# Boardv2.net
KiCad netlist of a schematic drawn in EAGLE
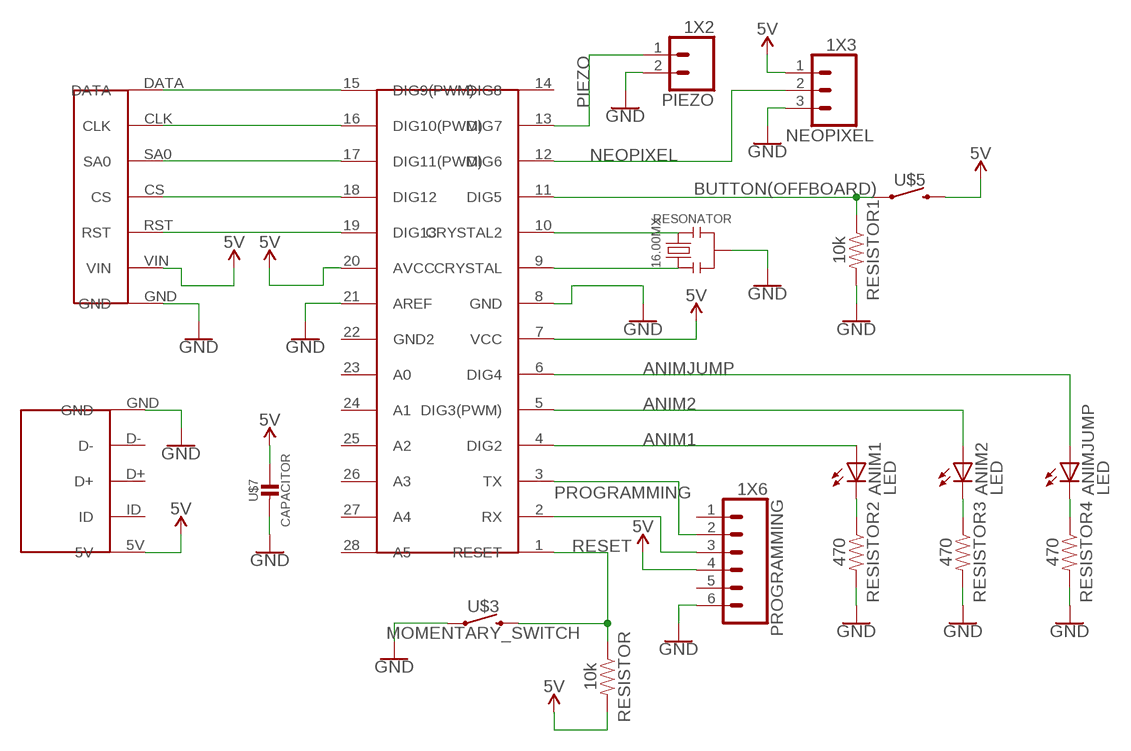
[diagram p0: schematic, sheet 1]

(export (version "E")
  (design (tool "Eeschema 10.0.6"))
  (components
    (comp (ref "16.00MX")
      (value "RESONATOR")
      (footprint "eagle-import:1X03_NO_SILK")
      (libsource (lib "eagle-import") (part "RESONATOR"))
    )
    (comp (ref "ANIM1")
      (value "LED")
      (footprint "eagle-import:1X02_LONGPADS")
      (libsource (lib "eagle-import") (part "LED"))
    )
    (comp (ref "ANIM2")
      (value "LED")
      (footprint "eagle-import:1X02_LONGPADS")
      (libsource (lib "eagle-import") (part "LED"))
    )
    (comp (ref "ANIMJUMP")
      (value "LED")
      (footprint "eagle-import:1X02_LONGPADS")
      (libsource (lib "eagle-import") (part "LED"))
    )
    (comp (ref "NEOPIXEL")
      (value "1X3")
      (footprint "eagle-import:1X03_NO_SILK")
      (libsource (lib "eagle-import") (part "1X3"))
    )
    (comp (ref "PIEZO")
      (value "1X2")
      (footprint "eagle-import:1X02_LONGPADS")
      (libsource (lib "eagle-import") (part "1X2"))
    )
    (comp (ref "PROGRAMMING")
      (value "1X6")
      (footprint "eagle-import:1X06_NO_SILK")
      (libsource (lib "eagle-import") (part "1X6"))
    )
    (comp (ref "RESISTOR")
      (value "10k")
      (footprint "eagle-import:AXIAL-0.3")
      (libsource (lib "eagle-import") (part "RESISTOR"))
    )
    (comp (ref "RESISTOR1")
      (value "10k")
      (footprint "eagle-import:AXIAL-0.3")
      (libsource (lib "eagle-import") (part "RESISTOR"))
    )
    (comp (ref "RESISTOR2")
      (value "470")
      (footprint "eagle-import:AXIAL-0.3")
      (libsource (lib "eagle-import") (part "RESISTOR"))
    )
    (comp (ref "RESISTOR3")
      (value "470")
      (footprint "eagle-import:AXIAL-0.3")
      (libsource (lib "eagle-import") (part "RESISTOR"))
    )
    (comp (ref "RESISTOR4")
      (value "470")
      (footprint "eagle-import:AXIAL-0.3")
      (libsource (lib "eagle-import") (part "RESISTOR"))
    )
    (comp (ref "U$1")
      (value "ATMEGA328")
      (footprint "eagle-import:ATMEGA328")
      (libsource (lib "eagle-import") (part "ATMEGA328"))
    )
    (comp (ref "U$2")
      (value "USB")
      (footprint "eagle-import:USB")
      (libsource (lib "eagle-import") (part "USB"))
    )
    (comp (ref "U$3")
      (value "MOMENTARY_SWITCH")
      (footprint "eagle-import:TACTILE_SWITCH_PTH_6.0MM")
      (libsource (lib "eagle-import") (part "MOMENTARY_SWITCH"))
    )
    (comp (ref "U$5")
      (value "BUTTON(OFFBOARD)")
      (footprint "eagle-import:1X02_LONGPADS")
      (libsource (lib "eagle-import") (part "BUTTON(OFFBOARD)"))
    )
    (comp (ref "U$6")
      (value "OLED")
      (footprint "eagle-import:OLED")
      (libsource (lib "eagle-import") (part "OLED"))
    )
    (comp (ref "U$7")
      (value "CAPACITOR")
      (footprint "eagle-import:1X02_LONGPADS")
      (libsource (lib "eagle-import") (part "CAPACITOR"))
    )
  )
  (nets
    (net (code "1") (name "/ANIM1") (class "Default")
      (node (ref "ANIM1") (pin "1") (pinfunction "A_1") (pintype "passive"))
      (node (ref "U$1") (pin "4") (pinfunction "DIG2_4") (pintype "bidirectional"))
    )
    (net (code "2") (name "/ANIM2") (class "Default")
      (node (ref "ANIM2") (pin "1") (pinfunction "A_1") (pintype "passive"))
      (node (ref "U$1") (pin "5") (pinfunction "DIG3(PWM)_5") (pintype "bidirectional"))
    )
    (net (code "3") (name "/ANIMJUMP") (class "Default")
      (node (ref "ANIMJUMP") (pin "1") (pinfunction "A_1") (pintype "passive"))
      (node (ref "U$1") (pin "6") (pinfunction "DIG4_6") (pintype "bidirectional"))
    )
    (net (code "4") (name "/NEOPIXEL") (class "Default")
      (node (ref "NEOPIXEL") (pin "2") (pinfunction "2_2") (pintype "passive"))
      (node (ref "U$1") (pin "12") (pinfunction "DIG6_12") (pintype "bidirectional"))
    )
    (net (code "5") (name "/PIEZO") (class "Default")
      (node (ref "PIEZO") (pin "1") (pinfunction "1_1") (pintype "passive"))
      (node (ref "U$1") (pin "13") (pinfunction "DIG7_13") (pintype "bidirectional"))
    )
    (net (code "6") (name "/PROGRAMMING") (class "Default")
      (node (ref "PROGRAMMING") (pin "2") (pinfunction "2_2") (pintype "passive"))
      (node (ref "U$1") (pin "3") (pinfunction "TX_3") (pintype "bidirectional"))
    )
    (net (code "7") (name "/RESET") (class "Default")
      (node (ref "RESISTOR") (pin "P$1") (pinfunction "1_P$1") (pintype "passive"))
      (node (ref "U$1") (pin "1") (pinfunction "RESET_1") (pintype "bidirectional"))
      (node (ref "U$3") (pin "3") (pinfunction "2_3") (pintype "passive"))
      (node (ref "U$3") (pin "4") (pinfunction "2_4") (pintype "passive"))
    )
    (net (code "8") (name "5V") (class "Default")
      (node (ref "NEOPIXEL") (pin "1") (pinfunction "1_1") (pintype "passive"))
      (node (ref "PROGRAMMING") (pin "4") (pinfunction "4_4") (pintype "passive"))
      (node (ref "RESISTOR") (pin "P$2") (pinfunction "2_P$2") (pintype "passive"))
      (node (ref "U$1") (pin "20") (pinfunction "AVCC_20") (pintype "bidirectional"))
      (node (ref "U$1") (pin "7") (pinfunction "VCC_7") (pintype "bidirectional"))
      (node (ref "U$2") (pin "5V") (pinfunction "5V_5V") (pintype "bidirectional"))
      (node (ref "U$5") (pin "2") (pinfunction "2_2") (pintype "passive"))
      (node (ref "U$6") (pin "VIN") (pinfunction "VIN_VIN") (pintype "bidirectional"))
      (node (ref "U$7") (pin "1") (pinfunction "1_1") (pintype "passive"))
    )
    (net (code "9") (name "GND") (class "Default")
      (node (ref "16.00MX") (pin "2") (pinfunction "2_2") (pintype "passive"))
      (node (ref "NEOPIXEL") (pin "3") (pinfunction "3_3") (pintype "passive"))
      (node (ref "PIEZO") (pin "2") (pinfunction "2_2") (pintype "passive"))
      (node (ref "PROGRAMMING") (pin "6") (pinfunction "6_6") (pintype "passive"))
      (node (ref "RESISTOR1") (pin "P$2") (pinfunction "2_P$2") (pintype "passive"))
      (node (ref "RESISTOR2") (pin "P$2") (pinfunction "2_P$2") (pintype "passive"))
      (node (ref "RESISTOR3") (pin "P$2") (pinfunction "2_P$2") (pintype "passive"))
      (node (ref "RESISTOR4") (pin "P$2") (pinfunction "2_P$2") (pintype "passive"))
      (node (ref "U$1") (pin "21") (pinfunction "AREF_21") (pintype "bidirectional"))
      (node (ref "U$1") (pin "8") (pinfunction "GND_8") (pintype "bidirectional"))
      (node (ref "U$2") (pin "GND") (pinfunction "GND_GND") (pintype "bidirectional"))
      (node (ref "U$3") (pin "1") (pinfunction "1_1") (pintype "passive"))
      (node (ref "U$3") (pin "2") (pinfunction "1_2") (pintype "passive"))
      (node (ref "U$6") (pin "GND") (pinfunction "GND_GND") (pintype "bidirectional"))
      (node (ref "U$7") (pin "2") (pinfunction "2_2") (pintype "passive"))
    )
    (net (code "10") (name "Net-(ANIM1-C)") (class "Default")
      (node (ref "ANIM1") (pin "2") (pinfunction "C_2") (pintype "passive"))
      (node (ref "RESISTOR2") (pin "P$1") (pinfunction "1_P$1") (pintype "passive"))
    )
    (net (code "11") (name "Net-(ANIM2-C)") (class "Default")
      (node (ref "ANIM2") (pin "2") (pinfunction "C_2") (pintype "passive"))
      (node (ref "RESISTOR3") (pin "P$1") (pinfunction "1_P$1") (pintype "passive"))
    )
    (net (code "12") (name "Net-(ANIMJUMP-C)") (class "Default")
      (node (ref "ANIMJUMP") (pin "2") (pinfunction "C_2") (pintype "passive"))
      (node (ref "RESISTOR4") (pin "P$1") (pinfunction "1_P$1") (pintype "passive"))
    )
    (net (code "13") (name "Net-(RESISTOR1-1)") (class "Default")
      (node (ref "RESISTOR1") (pin "P$1") (pinfunction "1_P$1") (pintype "passive"))
      (node (ref "U$1") (pin "11") (pinfunction "DIG5_11") (pintype "bidirectional"))
      (node (ref "U$5") (pin "1") (pinfunction "1_1") (pintype "passive"))
    )
    (net (code "14") (name "Net-(U$1-CRYSTAL)") (class "Default")
      (node (ref "16.00MX") (pin "1") (pinfunction "1_1") (pintype "passive"))
      (node (ref "U$1") (pin "9") (pinfunction "CRYSTAL_9") (pintype "bidirectional"))
    )
    (net (code "15") (name "Net-(U$1-CRYSTAL2)") (class "Default")
      (node (ref "16.00MX") (pin "3") (pinfunction "3_3") (pintype "passive"))
      (node (ref "U$1") (pin "10") (pinfunction "CRYSTAL2_10") (pintype "bidirectional"))
    )
    (net (code "16") (name "Net-(U$1-DIG9(PWM))") (class "Default")
      (node (ref "U$1") (pin "15") (pinfunction "DIG9(PWM)_15") (pintype "bidirectional"))
      (node (ref "U$6") (pin "DATA") (pinfunction "DATA_DATA") (pintype "bidirectional"))
    )
    (net (code "17") (name "Net-(U$1-DIG10(PWM))") (class "Default")
      (node (ref "U$1") (pin "16") (pinfunction "DIG10(PWM)_16") (pintype "bidirectional"))
      (node (ref "U$6") (pin "CLK") (pinfunction "CLK_CLK") (pintype "bidirectional"))
    )
    (net (code "18") (name "Net-(U$1-DIG11(PWM))") (class "Default")
      (node (ref "U$1") (pin "17") (pinfunction "DIG11(PWM)_17") (pintype "bidirectional"))
      (node (ref "U$6") (pin "SA0") (pinfunction "SA0_SA0") (pintype "bidirectional"))
    )
    (net (code "19") (name "Net-(U$1-DIG12)") (class "Default")
      (node (ref "U$1") (pin "18") (pinfunction "DIG12_18") (pintype "bidirectional"))
      (node (ref "U$6") (pin "CS") (pinfunction "CS_CS") (pintype "bidirectional"))
    )
    (net (code "20") (name "Net-(U$1-DIG13)") (class "Default")
      (node (ref "U$1") (pin "19") (pinfunction "DIG13_19") (pintype "bidirectional"))
      (node (ref "U$6") (pin "RST") (pinfunction "RST_RST") (pintype "bidirectional"))
    )
    (net (code "21") (name "Net-(U$1-RX)") (class "Default")
      (node (ref "PROGRAMMING") (pin "3") (pinfunction "3_3") (pintype "passive"))
      (node (ref "U$1") (pin "2") (pinfunction "RX_2") (pintype "bidirectional"))
    )
    (net (code "22") (name "unconnected-(PROGRAMMING-Pad1)") (class "Default")
      (node (ref "PROGRAMMING") (pin "1") (pinfunction "1_1") (pintype "passive"))
    )
    (net (code "23") (name "unconnected-(PROGRAMMING-Pad5)") (class "Default")
      (node (ref "PROGRAMMING") (pin "5") (pinfunction "5_5") (pintype "passive"))
    )
    (net (code "24") (name "unconnected-(U$1-A0-Pad23)") (class "Default")
      (node (ref "U$1") (pin "23") (pinfunction "A0_23") (pintype "bidirectional"))
    )
    (net (code "25") (name "unconnected-(U$1-A1-Pad24)") (class "Default")
      (node (ref "U$1") (pin "24") (pinfunction "A1_24") (pintype "bidirectional"))
    )
    (net (code "26") (name "unconnected-(U$1-A2-Pad25)") (class "Default")
      (node (ref "U$1") (pin "25") (pinfunction "A2_25") (pintype "bidirectional"))
    )
    (net (code "27") (name "unconnected-(U$1-A3-Pad26)") (class "Default")
      (node (ref "U$1") (pin "26") (pinfunction "A3_26") (pintype "bidirectional"))
    )
    (net (code "28") (name "unconnected-(U$1-A4-Pad27)") (class "Default")
      (node (ref "U$1") (pin "27") (pinfunction "A4_27") (pintype "bidirectional"))
    )
    (net (code "29") (name "unconnected-(U$1-A5-Pad28)") (class "Default")
      (node (ref "U$1") (pin "28") (pinfunction "A5_28") (pintype "bidirectional"))
    )
    (net (code "30") (name "unconnected-(U$1-DIG8-Pad14)") (class "Default")
      (node (ref "U$1") (pin "14") (pinfunction "DIG8_14") (pintype "bidirectional"))
    )
    (net (code "31") (name "unconnected-(U$1-GND2-Pad22)") (class "Default")
      (node (ref "U$1") (pin "22") (pinfunction "GND2_22") (pintype "bidirectional"))
    )
    (net (code "32") (name "unconnected-(U$2-PadD+)") (class "Default")
      (node (ref "U$2") (pin "D+") (pinfunction "D+_D+") (pintype "bidirectional"))
    )
    (net (code "33") (name "unconnected-(U$2-PadD-)") (class "Default")
      (node (ref "U$2") (pin "D-") (pinfunction "D-_D-") (pintype "bidirectional"))
    )
    (net (code "34") (name "unconnected-(U$2-PadID)") (class "Default")
      (node (ref "U$2") (pin "ID") (pinfunction "ID_ID") (pintype "bidirectional"))
    )
  )
)
